# AnalogIn.net
KiCad netlist of a schematic drawn in Altium Designer
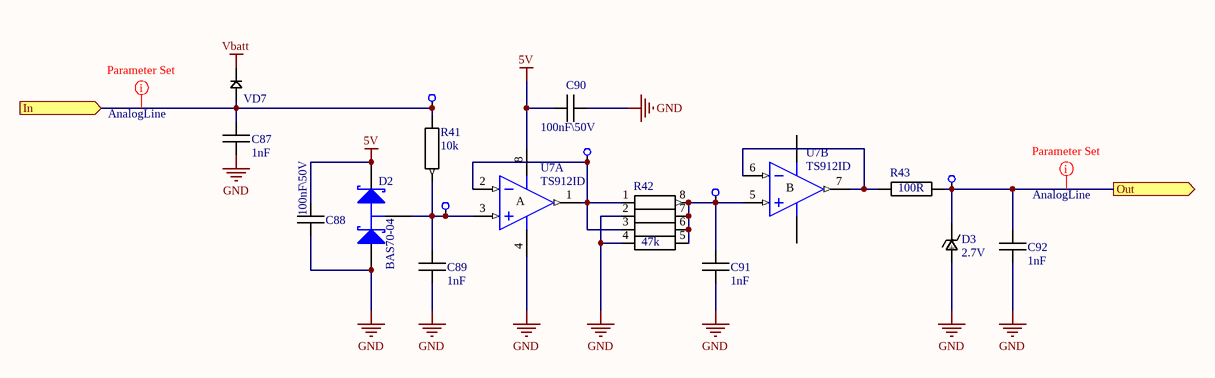
[diagram p0: AnalogIn.SchDoc]

(export (version "E")
  (design (tool "Eeschema 10.0.6"))
  (components
    (comp (ref "C87")
      (value "1nF")
      (footprint "SMD 0603")
      (description "CC0603KRX7R9BB102")
      (libsource (lib "Maks_lib") (part "Capasitor"))
    )
    (comp (ref "C88")
      (value "100n~{F}50V")
      (footprint "SMD 0603")
      (description "CC0603KRX7R9BB104")
      (libsource (lib "Maks_lib") (part "Capasitor"))
    )
    (comp (ref "C89")
      (value "1nF")
      (footprint "SMD 0603")
      (description "CC0603KRX7R9BB102")
      (libsource (lib "Maks_lib") (part "Capasitor"))
    )
    (comp (ref "C90")
      (value "100n~{F}50V")
      (footprint "SMD 0603")
      (description "CC0603KRX7R9BB104")
      (libsource (lib "Maks_lib") (part "Capasitor"))
    )
    (comp (ref "C91")
      (value "1nF")
      (footprint "SMD 0603")
      (description "CC0603KRX7R9BB102")
      (libsource (lib "Maks_lib") (part "Capasitor"))
    )
    (comp (ref "C92")
      (value "1nF")
      (footprint "SMD 0603")
      (description "CC0603KRX7R9BB102")
      (libsource (lib "Maks_lib") (part "Capasitor"))
    )
    (comp (ref "D2")
      (value "BAS70-04")
      (footprint "SOT23_N")
      (description "Schottky Barrier Double Diode")
      (fields (field (name "PUBLISHER") "Altium Limited"))
      (libsource (lib "altium-import") (part "root_1_mirrored_BAS70-04_"))
    )
    (comp (ref "D3")
      (value "2.7V")
      (footprint "SOD123")
      (description "MMSZ2V7T1G")
      (libsource (lib "Maks_lib") (part "Zener"))
    )
    (comp (ref "R41")
      (value "10k")
      (footprint "SMD 0603")
      (description "RC0603FR-0710KL")
      (libsource (lib "Maks_lib") (part "Resistor"))
    )
    (comp (ref "R42")
      (value "47k")
      (footprint "YC164")
      (description "YC164-JR-0747KL")
      (libsource (lib "Maks_lib") (part "YC164"))
    )
    (comp (ref "R43")
      (value "100R")
      (footprint "SMD 0603")
      (description "RC0603FR-07100RL")
      (libsource (lib "") (part "Resistor_1"))
    )
    (comp (ref "TP59")
      (value "TestPoint")
      (footprint "TESTPOINT")
      (description "testPoint")
      (libsource (lib "Maks_lib") (part "TestPoint"))
    )
    (comp (ref "TP60")
      (value "TestPoint")
      (footprint "TESTPOINT")
      (description "testPoint")
      (libsource (lib "Maks_lib") (part "TestPoint"))
    )
    (comp (ref "TP61")
      (value "TestPoint")
      (footprint "TESTPOINT")
      (description "testPoint")
      (libsource (lib "Maks_lib") (part "TestPoint"))
    )
    (comp (ref "TP62")
      (value "TestPoint")
      (footprint "TESTPOINT")
      (description "testPoint")
      (libsource (lib "Maks_lib") (part "TestPoint"))
    )
    (comp (ref "TP63")
      (value "TestPoint")
      (footprint "TESTPOINT")
      (description "testPoint")
      (libsource (lib "Maks_lib") (part "TestPoint"))
    )
    (comp (ref "U7")
      (value "TS912ID")
      (footprint "SO8_N")
      (description "Rail-to-Rail CMOS Dual Operational Amplifier")
      (fields (field (name "PUBLISHER") "Altium Limited"))
      (libsource (lib "") (part "TS912ID_1"))
    )
    (comp (ref "VD7")
      (value "Diode")
      (footprint "SOD323")
      (description "PMEG2020EJ.115")
      (libsource (lib "Maks_lib") (part "Diode"))
    )
  )
  (nets
    (net (code "1") (name "/In") (class "Default")
      (node (ref "C87") (pin "2") (pinfunction "2_2") (pintype "passive"))
      (node (ref "R41") (pin "1") (pinfunction "1_1") (pintype "passive"))
      (node (ref "TP59") (pin "0") (pinfunction "0_0") (pintype "passive"))
      (node (ref "VD7") (pin "0") (pinfunction "0_0") (pintype "passive"))
    )
    (net (code "2") (name "/Out") (class "Default")
      (node (ref "C92") (pin "2") (pinfunction "2_2") (pintype "passive"))
      (node (ref "D3") (pin "+") (pinfunction "+_+") (pintype "passive"))
      (node (ref "R43") (pin "2") (pinfunction "2_2") (pintype "passive"))
      (node (ref "TP63") (pin "0") (pinfunction "0_0") (pintype "passive"))
    )
    (net (code "3") (name "5V") (class "Default")
      (node (ref "C88") (pin "1") (pinfunction "1_1") (pintype "passive"))
      (node (ref "C90") (pin "2") (pinfunction "2_2") (pintype "passive"))
      (node (ref "D2") (pin "2") (pinfunction "K_2") (pintype "passive"))
      (node (ref "U7") (pin "8") (pinfunction "V+_8") (pintype "passive"))
    )
    (net (code "4") (name "GND") (class "Default")
      (node (ref "C87") (pin "1") (pinfunction "1_1") (pintype "passive"))
      (node (ref "C88") (pin "2") (pinfunction "2_2") (pintype "passive"))
      (node (ref "C89") (pin "1") (pinfunction "1_1") (pintype "passive"))
      (node (ref "C90") (pin "1") (pinfunction "1_1") (pintype "passive"))
      (node (ref "C91") (pin "1") (pinfunction "1_1") (pintype "passive"))
      (node (ref "C92") (pin "1") (pinfunction "1_1") (pintype "passive"))
      (node (ref "D2") (pin "1") (pinfunction "A_1") (pintype "passive"))
      (node (ref "D3") (pin "-") (pinfunction "-_-") (pintype "passive"))
      (node (ref "R42") (pin "2") (pinfunction "2_2") (pintype "passive"))
      (node (ref "R42") (pin "4") (pinfunction "4_4") (pintype "passive"))
      (node (ref "U7") (pin "4") (pinfunction "V-_4") (pintype "passive"))
    )
    (net (code "5") (name "Net-(D2-C)") (class "Default")
      (node (ref "C89") (pin "2") (pinfunction "2_2") (pintype "passive"))
      (node (ref "D2") (pin "3") (pinfunction "C_3") (pintype "passive"))
      (node (ref "R41") (pin "2") (pinfunction "2_2") (pintype "output"))
      (node (ref "TP60") (pin "0") (pinfunction "0_0") (pintype "passive"))
      (node (ref "U7") (pin "3") (pinfunction "IN+_3") (pintype "input"))
    )
    (net (code "6") (name "Net-(U7A-IN-)") (class "Default")
      (node (ref "R42") (pin "1") (pinfunction "1_1") (pintype "passive"))
      (node (ref "R42") (pin "3") (pinfunction "3_3") (pintype "passive"))
      (node (ref "TP61") (pin "0") (pinfunction "0_0") (pintype "passive"))
      (node (ref "U7") (pin "1") (pinfunction "OUT_1") (pintype "output"))
      (node (ref "U7") (pin "2") (pinfunction "IN-_2") (pintype "input"))
    )
    (net (code "7") (name "Net-(U7B-IN+)") (class "Default")
      (node (ref "C91") (pin "2") (pinfunction "2_2") (pintype "passive"))
      (node (ref "R42") (pin "5") (pinfunction "5_5") (pintype "passive"))
      (node (ref "R42") (pin "6") (pinfunction "6_6") (pintype "passive"))
      (node (ref "R42") (pin "7") (pinfunction "7_7") (pintype "passive"))
      (node (ref "R42") (pin "8") (pinfunction "8_8") (pintype "output"))
      (node (ref "TP62") (pin "0") (pinfunction "0_0") (pintype "passive"))
      (node (ref "U7") (pin "5") (pinfunction "IN+_5") (pintype "input"))
    )
    (net (code "8") (name "Net-(U7B-IN-)") (class "Default")
      (node (ref "R43") (pin "1") (pinfunction "1_1") (pintype "passive"))
      (node (ref "U7") (pin "6") (pinfunction "IN-_6") (pintype "input"))
      (node (ref "U7") (pin "7") (pinfunction "OUT_7") (pintype "output"))
    )
    (net (code "9") (name "Vbatt") (class "Default")
      (node (ref "VD7") (pin "1") (pinfunction "1_1") (pintype "passive"))
    )
    (net (code "10") (name "unconnected-(U7B-V+-Pad18)") (class "Default")
      (node (ref "U7") (pin "18") (pinfunction "V+_18") (pintype "power_in"))
    )
    (net (code "11") (name "unconnected-(U7B-V--Pad14)") (class "Default")
      (node (ref "U7") (pin "14") (pinfunction "V-_14") (pintype "passive"))
    )
  )
)
